# USB2_0_Connector.net
KiCad netlist of a schematic drawn in Altium Designer
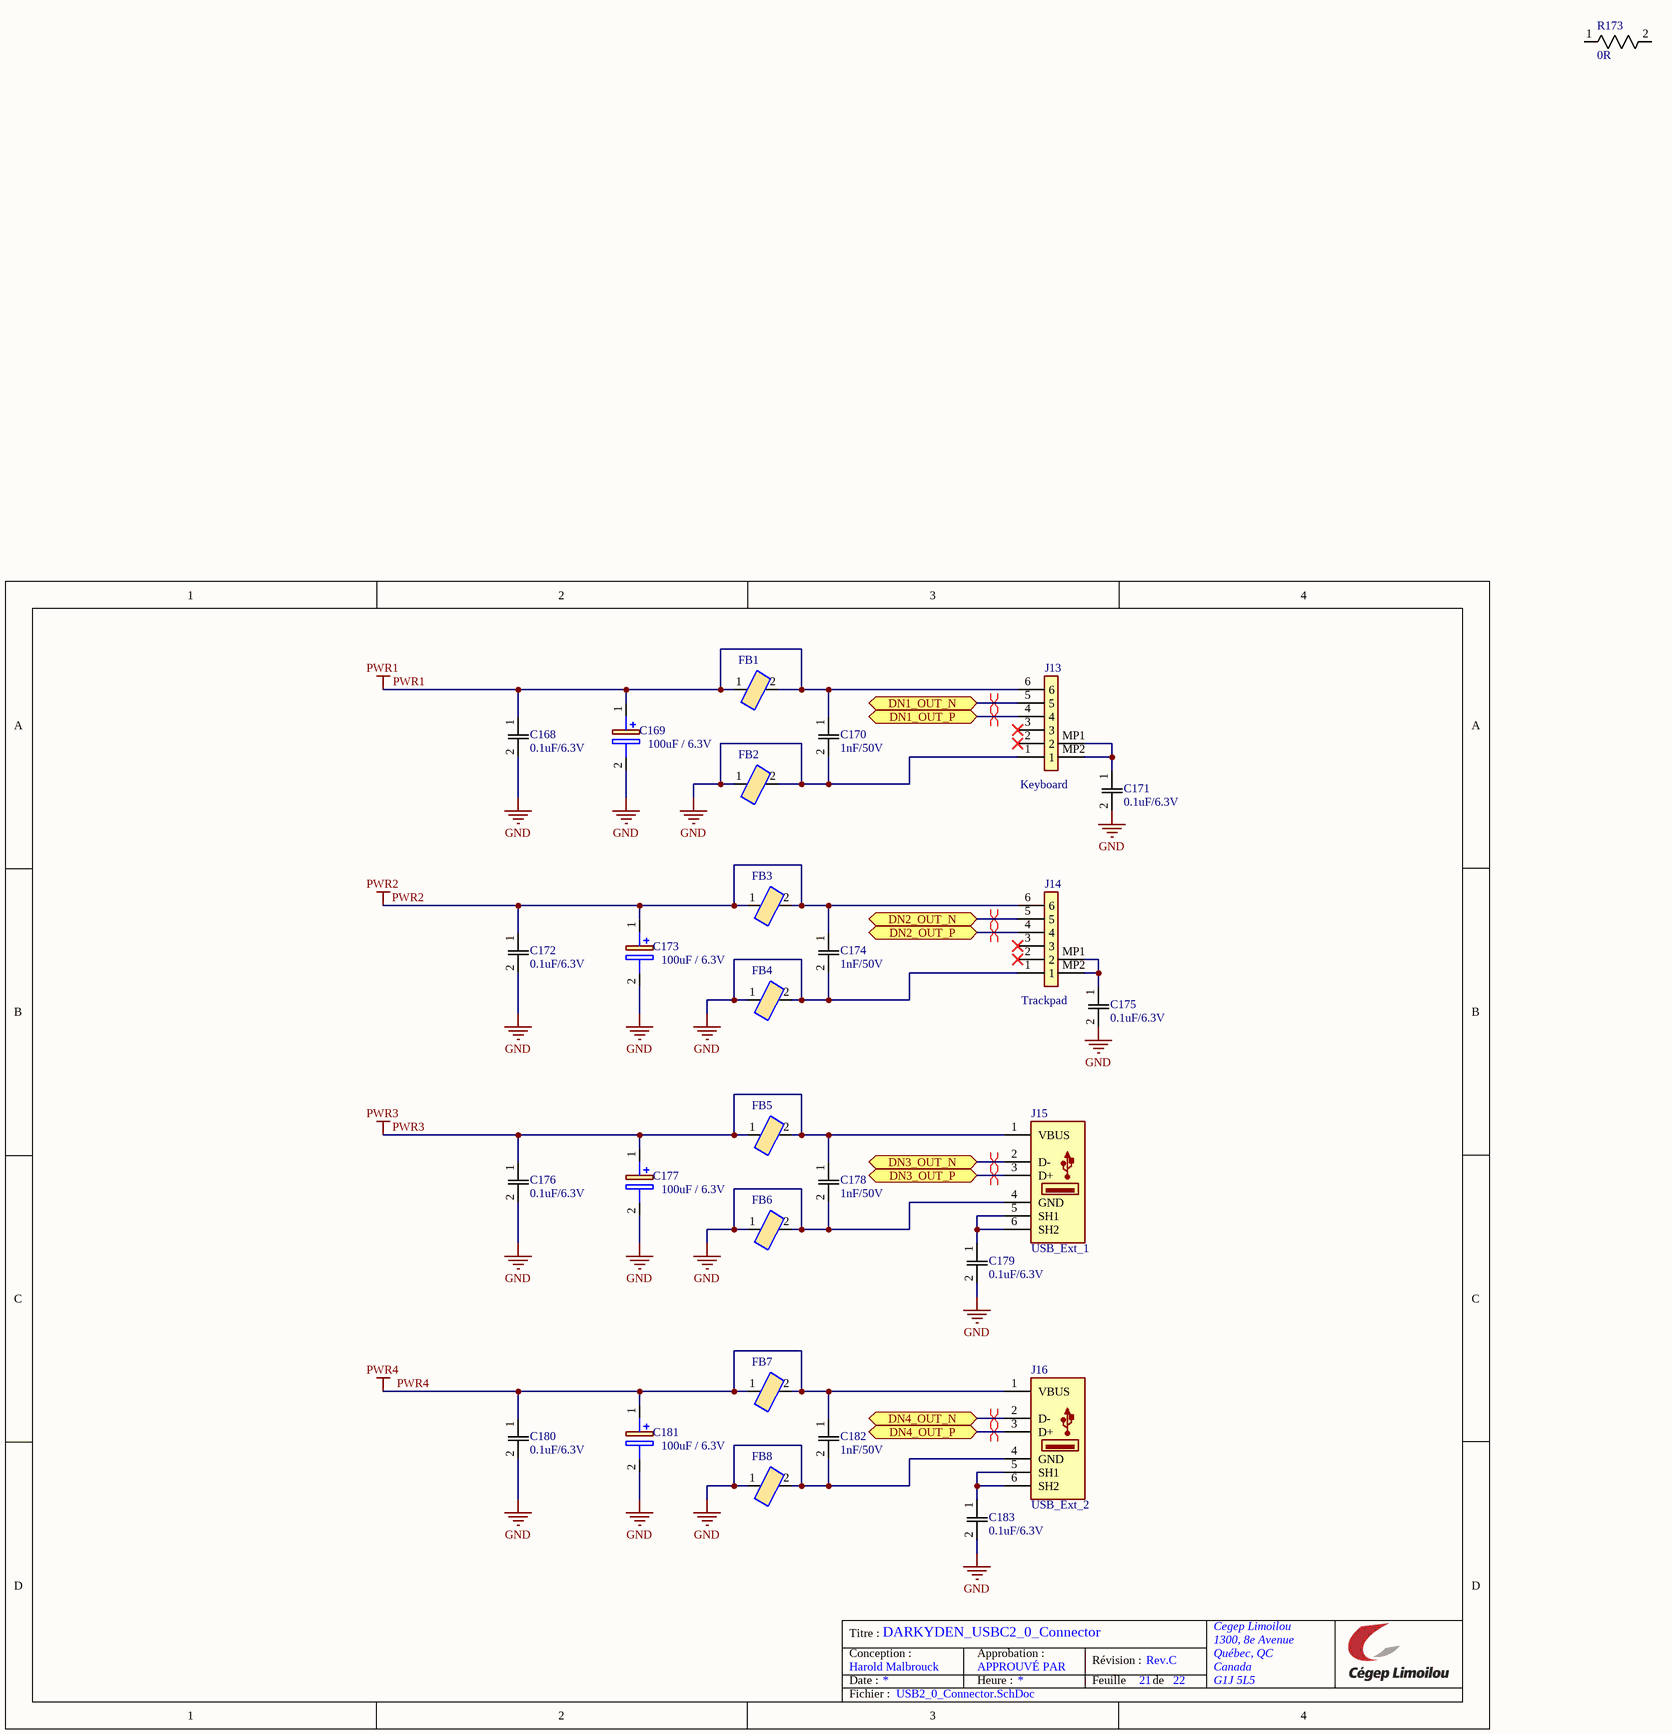
[diagram p0: USB2_0_Connector.SchDoc]

(export (version "E")
  (design (tool "Eeschema 10.0.6"))
  (components
    (comp (ref "C168")
      (value "0.1uF/6.3V")
      (footprint "SamacSys:C0805")
      (description "0.1uF 6.3V X7R 10% Pad SMD 0805 125C T/R")
      (fields
        (field (name "MANUFACTURER_PART_NUMBER") "C0805C104K9RACTU")
        (field (name "MOUSER PART NUMBER") "80-C0805C104K9R")
      )
      (libsource (lib "SamacSys") (part "C0805C104K9RACTU"))
    )
    (comp (ref "C169")
      (value "100uF / 6.3V")
      (footprint "SamacSys:EEE0GA101SR")
      (description "100uF 6.3V 20% Cap Aluminum Lytic  SMD 0.36 Ohm 240mA 2000h 105C Automotive T/R")
      (fields
        (field (name "MANUFACTURER_PART_NUMBER") "EEE-FPJ101UAR")
        (field (name "MOUSER PART NUMBER") "667-EEE-FPJ101UAR")
      )
      (libsource (lib "SamacSys") (part "EEE-FPJ101UAR"))
    )
    (comp (ref "C170")
      (value "1nF/50V")
      (footprint "SamacSys:CAPC2012X88N")
      (description "Multilayer Ceramic Capacitor 1000 Pf 50 V ½ 10% X7R 0805 [2012 Metric]")
      (fields
        (field (name "MANUFACTURER_PART_NUMBER") "C0805C102K5RAC-TU")
        (field (name "MANUFACTURER") "KEMET")
      )
      (libsource (lib "SamacSys") (part "C0805C102K5RACTU"))
    )
    (comp (ref "C171")
      (value "0.1uF/6.3V")
      (footprint "SamacSys:C0805")
      (description "0.1uF 6.3V X7R 10% Pad SMD 0805 125C T/R")
      (fields
        (field (name "MANUFACTURER_PART_NUMBER") "C0805C104K9RACTU")
        (field (name "MOUSER PART NUMBER") "80-C0805C104K9R")
      )
      (libsource (lib "SamacSys") (part "C0805C104K9RACTU"))
    )
    (comp (ref "C172")
      (value "0.1uF/6.3V")
      (footprint "SamacSys:C0805")
      (description "0.1uF 6.3V X7R 10% Pad SMD 0805 125C T/R")
      (fields
        (field (name "MANUFACTURER_PART_NUMBER") "C0805C104K9RACTU")
        (field (name "MOUSER PART NUMBER") "80-C0805C104K9R")
      )
      (libsource (lib "SamacSys") (part "C0805C104K9RACTU"))
    )
    (comp (ref "C173")
      (value "100uF / 6.3V")
      (footprint "SamacSys:EEE0GA101SR")
      (description "100uF 6.3V 20% Cap Aluminum Lytic  SMD 0.36 Ohm 240mA 2000h 105C Automotive T/R")
      (fields
        (field (name "MANUFACTURER_PART_NUMBER") "EEE-FPJ101UAR")
        (field (name "MOUSER PART NUMBER") "667-EEE-FPJ101UAR")
      )
      (libsource (lib "SamacSys") (part "EEE-FPJ101UAR"))
    )
    (comp (ref "C174")
      (value "1nF/50V")
      (footprint "SamacSys:CAPC2012X88N")
      (description "Multilayer Ceramic Capacitor 1000 Pf 50 V ½ 10% X7R 0805 [2012 Metric]")
      (fields
        (field (name "MANUFACTURER_PART_NUMBER") "C0805C102K5RAC-TU")
        (field (name "MANUFACTURER") "KEMET")
      )
      (libsource (lib "SamacSys") (part "C0805C102K5RACTU"))
    )
    (comp (ref "C175")
      (value "0.1uF/6.3V")
      (footprint "SamacSys:C0805")
      (description "0.1uF 6.3V X7R 10% Pad SMD 0805 125C T/R")
      (fields
        (field (name "MANUFACTURER_PART_NUMBER") "C0805C104K9RACTU")
        (field (name "MOUSER PART NUMBER") "80-C0805C104K9R")
      )
      (libsource (lib "SamacSys") (part "C0805C104K9RACTU"))
    )
    (comp (ref "C176")
      (value "0.1uF/6.3V")
      (footprint "SamacSys:C0805")
      (description "0.1uF 6.3V X7R 10% Pad SMD 0805 125C T/R")
      (fields
        (field (name "MANUFACTURER_PART_NUMBER") "C0805C104K9RACTU")
        (field (name "MOUSER PART NUMBER") "80-C0805C104K9R")
      )
      (libsource (lib "SamacSys") (part "C0805C104K9RACTU"))
    )
    (comp (ref "C177")
      (value "100uF / 6.3V")
      (footprint "SamacSys:EEE0GA101SR")
      (description "100uF 6.3V 20% Cap Aluminum Lytic  SMD 0.36 Ohm 240mA 2000h 105C Automotive T/R")
      (fields
        (field (name "MANUFACTURER_PART_NUMBER") "EEE-FPJ101UAR")
        (field (name "MOUSER PART NUMBER") "667-EEE-FPJ101UAR")
      )
      (libsource (lib "SamacSys") (part "EEE-FPJ101UAR"))
    )
    (comp (ref "C178")
      (value "1nF/50V")
      (footprint "SamacSys:CAPC2012X88N")
      (description "Multilayer Ceramic Capacitor 1000 Pf 50 V ½ 10% X7R 0805 [2012 Metric]")
      (fields
        (field (name "MANUFACTURER_PART_NUMBER") "C0805C102K5RAC-TU")
        (field (name "MANUFACTURER") "KEMET")
      )
      (libsource (lib "SamacSys") (part "C0805C102K5RACTU"))
    )
    (comp (ref "C179")
      (value "0.1uF/6.3V")
      (footprint "SamacSys:C0805")
      (description "0.1uF 6.3V X7R 10% Pad SMD 0805 125C T/R")
      (fields
        (field (name "MANUFACTURER_PART_NUMBER") "C0805C104K9RACTU")
        (field (name "MOUSER PART NUMBER") "80-C0805C104K9R")
      )
      (libsource (lib "SamacSys") (part "C0805C104K9RACTU"))
    )
    (comp (ref "C180")
      (value "0.1uF/6.3V")
      (footprint "SamacSys:C0805")
      (description "0.1uF 6.3V X7R 10% Pad SMD 0805 125C T/R")
      (fields
        (field (name "MANUFACTURER_PART_NUMBER") "C0805C104K9RACTU")
        (field (name "MOUSER PART NUMBER") "80-C0805C104K9R")
      )
      (libsource (lib "SamacSys") (part "C0805C104K9RACTU"))
    )
    (comp (ref "C181")
      (value "100uF / 6.3V")
      (footprint "SamacSys:EEE0GA101SR")
      (description "100uF 6.3V 20% Cap Aluminum Lytic  SMD 0.36 Ohm 240mA 2000h 105C Automotive T/R")
      (fields
        (field (name "MANUFACTURER_PART_NUMBER") "EEE-FPJ101UAR")
        (field (name "MOUSER PART NUMBER") "667-EEE-FPJ101UAR")
      )
      (libsource (lib "SamacSys") (part "EEE-FPJ101UAR"))
    )
    (comp (ref "C182")
      (value "1nF/50V")
      (footprint "SamacSys:CAPC2012X88N")
      (description "Multilayer Ceramic Capacitor 1000 Pf 50 V ½ 10% X7R 0805 [2012 Metric]")
      (fields
        (field (name "MANUFACTURER_PART_NUMBER") "C0805C102K5RAC-TU")
        (field (name "MANUFACTURER") "KEMET")
      )
      (libsource (lib "SamacSys") (part "C0805C102K5RACTU"))
    )
    (comp (ref "C183")
      (value "0.1uF/6.3V")
      (footprint "SamacSys:C0805")
      (description "0.1uF 6.3V X7R 10% Pad SMD 0805 125C T/R")
      (fields
        (field (name "MANUFACTURER_PART_NUMBER") "C0805C104K9RACTU")
        (field (name "MOUSER PART NUMBER") "80-C0805C104K9R")
      )
      (libsource (lib "SamacSys") (part "C0805C104K9RACTU"))
    )
    (comp (ref "FB1")
      (value "220R / 100MHz")
      (footprint "SamacSys:BLM18SP221SN1B")
      (description "Ferrite Beads Multi-Layer 220Ohm 25% 100MHz 2A 50mOhm DCR 0603 Paper T/R")
      (fields
        (field (name "MANUFACTURER_PART_NUMBER") "BLM18EG221SN1D")
        (field (name "MOUSER PART NUMBER") "81-BLM18EG221SN1D")
      )
      (libsource (lib "SamacSys") (part "BLM18EG221SN1D"))
    )
    (comp (ref "FB2")
      (value "220R / 100MHz")
      (footprint "SamacSys:BLM18SP221SN1B")
      (description "Ferrite Beads Multi-Layer 220Ohm 25% 100MHz 2A 50mOhm DCR 0603 Paper T/R")
      (fields
        (field (name "MANUFACTURER_PART_NUMBER") "BLM18EG221SN1D")
        (field (name "MOUSER PART NUMBER") "81-BLM18EG221SN1D")
      )
      (libsource (lib "SamacSys") (part "BLM18EG221SN1D"))
    )
    (comp (ref "FB3")
      (value "220R / 100MHz")
      (footprint "SamacSys:BLM18SP221SN1B")
      (description "Ferrite Beads Multi-Layer 220Ohm 25% 100MHz 2A 50mOhm DCR 0603 Paper T/R")
      (fields
        (field (name "MANUFACTURER_PART_NUMBER") "BLM18EG221SN1D")
        (field (name "MOUSER PART NUMBER") "81-BLM18EG221SN1D")
      )
      (libsource (lib "SamacSys") (part "BLM18EG221SN1D"))
    )
    (comp (ref "FB4")
      (value "220R / 100MHz")
      (footprint "SamacSys:BLM18SP221SN1B")
      (description "Ferrite Beads Multi-Layer 220Ohm 25% 100MHz 2A 50mOhm DCR 0603 Paper T/R")
      (fields
        (field (name "MANUFACTURER_PART_NUMBER") "BLM18EG221SN1D")
        (field (name "MOUSER PART NUMBER") "81-BLM18EG221SN1D")
      )
      (libsource (lib "SamacSys") (part "BLM18EG221SN1D"))
    )
    (comp (ref "FB5")
      (value "220R / 100MHz")
      (footprint "SamacSys:BLM18SP221SN1B")
      (description "Ferrite Beads Multi-Layer 220Ohm 25% 100MHz 2A 50mOhm DCR 0603 Paper T/R")
      (fields
        (field (name "MANUFACTURER_PART_NUMBER") "BLM18EG221SN1D")
        (field (name "MOUSER PART NUMBER") "81-BLM18EG221SN1D")
      )
      (libsource (lib "SamacSys") (part "BLM18EG221SN1D"))
    )
    (comp (ref "FB6")
      (value "220R / 100MHz")
      (footprint "SamacSys:BLM18SP221SN1B")
      (description "Ferrite Beads Multi-Layer 220Ohm 25% 100MHz 2A 50mOhm DCR 0603 Paper T/R")
      (fields
        (field (name "MANUFACTURER_PART_NUMBER") "BLM18EG221SN1D")
        (field (name "MOUSER PART NUMBER") "81-BLM18EG221SN1D")
      )
      (libsource (lib "SamacSys") (part "BLM18EG221SN1D"))
    )
    (comp (ref "FB7")
      (value "220R / 100MHz")
      (footprint "SamacSys:BLM18SP221SN1B")
      (description "Ferrite Beads Multi-Layer 220Ohm 25% 100MHz 2A 50mOhm DCR 0603 Paper T/R")
      (fields
        (field (name "MANUFACTURER_PART_NUMBER") "BLM18EG221SN1D")
        (field (name "MOUSER PART NUMBER") "81-BLM18EG221SN1D")
      )
      (libsource (lib "SamacSys") (part "BLM18EG221SN1D"))
    )
    (comp (ref "FB8")
      (value "220R / 100MHz")
      (footprint "SamacSys:BLM18SP221SN1B")
      (description "Ferrite Beads Multi-Layer 220Ohm 25% 100MHz 2A 50mOhm DCR 0603 Paper T/R")
      (fields
        (field (name "MANUFACTURER_PART_NUMBER") "BLM18EG221SN1D")
        (field (name "MOUSER PART NUMBER") "81-BLM18EG221SN1D")
      )
      (libsource (lib "SamacSys") (part "BLM18EG221SN1D"))
    )
    (comp (ref "J13")
      (value "Keyboard")
      (footprint "SamacSys:23287026")
      (description "FPC Connector; 0.5mm pitch dual contact back flip FPC, 6pos ¦ TE Connectivity 2328702-6")
      (fields
        (field (name "MANUFACTURER_PART_NUMBER") "2328702-6")
        (field (name "MOUSER PART NUMBER") "571-2328702-6")
      )
      (libsource (lib "SamacSys") (part "2328702-6"))
    )
    (comp (ref "J14")
      (value "Trackpad")
      (footprint "SamacSys:23287026")
      (description "FPC Connector; 0.5mm pitch dual contact back flip FPC, 6pos ¦ TE Connectivity 2328702-6")
      (fields
        (field (name "MANUFACTURER_PART_NUMBER") "2328702-6")
        (field (name "MOUSER PART NUMBER") "571-2328702-6")
      )
      (libsource (lib "SamacSys") (part "2328702-6"))
    )
    (comp (ref "J15")
      (value "USB_Ext_1")
      (footprint "SamacSys:TECONN-4POS-USB")
      (description "USB-A (USB TYPE-A) USB 2.0 Receptacle Connector 4 Position Through Hole, Right Angle")
      (fields
        (field (name "MANUFACTURER_PART_NUMBER") "292303-1")
        (field (name "MOUSER PART NUMBER") "571-292303-1")
      )
      (libsource (lib "SamacSys") (part "292303-1"))
    )
    (comp (ref "J16")
      (value "USB_Ext_2")
      (footprint "SamacSys:TECONN-4POS-USB")
      (description "USB-A (USB TYPE-A) USB 2.0 Receptacle Connector 4 Position Through Hole, Right Angle")
      (fields
        (field (name "MANUFACTURER_PART_NUMBER") "292303-1")
        (field (name "MOUSER PART NUMBER") "571-292303-1")
      )
      (libsource (lib "SamacSys") (part "292303-1"))
    )
    (comp (ref "R173")
      (value "0R")
      (footprint "SamacSys:ERJ3EKF1000V")
      (description "Zero Ohm Resistor, Jumper, 0603 [1608 Metric], Thick Film, 100 mW, 1 A, Surface Mount")
      (fields
        (field (name "MANUFACTURER_PART_NUMBER") "ERJ-3GEY0R00V")
        (field (name "MOUSER PART NUMBER") "667-ERJ-3GEY0R00V")
      )
      (libsource (lib "SamacSys") (part "ERJ-3GEY0R00V"))
    )
  )
  (nets
    (net (code "1") (name "/DN1_OUT_N") (class "Default")
      (node (ref "J13") (pin "5") (pinfunction "5_5") (pintype "passive"))
    )
    (net (code "2") (name "/DN1_OUT_P") (class "Default")
      (node (ref "J13") (pin "4") (pinfunction "4_4") (pintype "passive"))
    )
    (net (code "3") (name "/DN2_OUT_N") (class "Default")
      (node (ref "J14") (pin "5") (pinfunction "5_5") (pintype "passive"))
    )
    (net (code "4") (name "/DN2_OUT_P") (class "Default")
      (node (ref "J14") (pin "4") (pinfunction "4_4") (pintype "passive"))
    )
    (net (code "5") (name "/DN3_OUT_N") (class "Default")
      (node (ref "J15") (pin "2") (pinfunction "D-_2") (pintype "passive"))
    )
    (net (code "6") (name "/DN3_OUT_P") (class "Default")
      (node (ref "J15") (pin "3") (pinfunction "D+_3") (pintype "passive"))
    )
    (net (code "7") (name "/DN4_OUT_N") (class "Default")
      (node (ref "J16") (pin "2") (pinfunction "D-_2") (pintype "passive"))
    )
    (net (code "8") (name "/DN4_OUT_P") (class "Default")
      (node (ref "J16") (pin "3") (pinfunction "D+_3") (pintype "passive"))
    )
    (net (code "9") (name "GND") (class "Default")
      (node (ref "C168") (pin "2") (pinfunction "2_2") (pintype "passive"))
      (node (ref "C169") (pin "2") (pinfunction "-_2") (pintype "passive"))
      (node (ref "C170") (pin "2") (pinfunction "2_2") (pintype "passive"))
      (node (ref "C171") (pin "2") (pinfunction "2_2") (pintype "passive"))
      (node (ref "C172") (pin "2") (pinfunction "2_2") (pintype "passive"))
      (node (ref "C173") (pin "2") (pinfunction "-_2") (pintype "passive"))
      (node (ref "C174") (pin "2") (pinfunction "2_2") (pintype "passive"))
      (node (ref "C175") (pin "2") (pinfunction "2_2") (pintype "passive"))
      (node (ref "C176") (pin "2") (pinfunction "2_2") (pintype "passive"))
      (node (ref "C177") (pin "2") (pinfunction "-_2") (pintype "passive"))
      (node (ref "C178") (pin "2") (pinfunction "2_2") (pintype "passive"))
      (node (ref "C179") (pin "2") (pinfunction "2_2") (pintype "passive"))
      (node (ref "C180") (pin "2") (pinfunction "2_2") (pintype "passive"))
      (node (ref "C181") (pin "2") (pinfunction "-_2") (pintype "passive"))
      (node (ref "C182") (pin "2") (pinfunction "2_2") (pintype "passive"))
      (node (ref "C183") (pin "2") (pinfunction "2_2") (pintype "passive"))
      (node (ref "FB2") (pin "1") (pinfunction "1_1") (pintype "passive"))
      (node (ref "FB2") (pin "2") (pinfunction "2_2") (pintype "passive"))
      (node (ref "FB4") (pin "1") (pinfunction "1_1") (pintype "passive"))
      (node (ref "FB4") (pin "2") (pinfunction "2_2") (pintype "passive"))
      (node (ref "FB6") (pin "1") (pinfunction "1_1") (pintype "passive"))
      (node (ref "FB6") (pin "2") (pinfunction "2_2") (pintype "passive"))
      (node (ref "FB8") (pin "1") (pinfunction "1_1") (pintype "passive"))
      (node (ref "FB8") (pin "2") (pinfunction "2_2") (pintype "passive"))
      (node (ref "J13") (pin "1") (pinfunction "1_1") (pintype "passive"))
      (node (ref "J14") (pin "1") (pinfunction "1_1") (pintype "passive"))
      (node (ref "J15") (pin "4") (pinfunction "GND_4") (pintype "passive"))
      (node (ref "J16") (pin "4") (pinfunction "GND_4") (pintype "passive"))
    )
    (net (code "10") (name "Net-(C171-Pad1)") (class "Default")
      (node (ref "C171") (pin "1") (pinfunction "1_1") (pintype "passive"))
      (node (ref "J13") (pin "MP1") (pinfunction "MP1_MP1") (pintype "passive"))
      (node (ref "J13") (pin "MP2") (pinfunction "MP2_MP2") (pintype "passive"))
    )
    (net (code "11") (name "Net-(C175-Pad1)") (class "Default")
      (node (ref "C175") (pin "1") (pinfunction "1_1") (pintype "passive"))
      (node (ref "J14") (pin "MP1") (pinfunction "MP1_MP1") (pintype "passive"))
      (node (ref "J14") (pin "MP2") (pinfunction "MP2_MP2") (pintype "passive"))
    )
    (net (code "12") (name "Net-(J15-SH1)") (class "Default")
      (node (ref "C179") (pin "1") (pinfunction "1_1") (pintype "passive"))
      (node (ref "J15") (pin "5") (pinfunction "SH1_5") (pintype "passive"))
      (node (ref "J15") (pin "6") (pinfunction "SH2_6") (pintype "passive"))
    )
    (net (code "13") (name "Net-(J16-SH1)") (class "Default")
      (node (ref "C183") (pin "1") (pinfunction "1_1") (pintype "passive"))
      (node (ref "J16") (pin "5") (pinfunction "SH1_5") (pintype "passive"))
      (node (ref "J16") (pin "6") (pinfunction "SH2_6") (pintype "passive"))
    )
    (net (code "14") (name "PWR1") (class "Default")
      (node (ref "C168") (pin "1") (pinfunction "1_1") (pintype "passive"))
      (node (ref "C169") (pin "1") (pinfunction "+_1") (pintype "passive"))
      (node (ref "C170") (pin "1") (pinfunction "1_1") (pintype "passive"))
      (node (ref "FB1") (pin "1") (pinfunction "1_1") (pintype "passive"))
      (node (ref "FB1") (pin "2") (pinfunction "2_2") (pintype "passive"))
      (node (ref "J13") (pin "6") (pinfunction "6_6") (pintype "passive"))
    )
    (net (code "15") (name "PWR2") (class "Default")
      (node (ref "C172") (pin "1") (pinfunction "1_1") (pintype "passive"))
      (node (ref "C173") (pin "1") (pinfunction "+_1") (pintype "passive"))
      (node (ref "C174") (pin "1") (pinfunction "1_1") (pintype "passive"))
      (node (ref "FB3") (pin "1") (pinfunction "1_1") (pintype "passive"))
      (node (ref "FB3") (pin "2") (pinfunction "2_2") (pintype "passive"))
      (node (ref "J14") (pin "6") (pinfunction "6_6") (pintype "passive"))
    )
    (net (code "16") (name "PWR3") (class "Default")
      (node (ref "C176") (pin "1") (pinfunction "1_1") (pintype "passive"))
      (node (ref "C177") (pin "1") (pinfunction "+_1") (pintype "passive"))
      (node (ref "C178") (pin "1") (pinfunction "1_1") (pintype "passive"))
      (node (ref "FB5") (pin "1") (pinfunction "1_1") (pintype "passive"))
      (node (ref "FB5") (pin "2") (pinfunction "2_2") (pintype "passive"))
      (node (ref "J15") (pin "1") (pinfunction "VBUS_1") (pintype "passive"))
    )
    (net (code "17") (name "PWR4") (class "Default")
      (node (ref "C180") (pin "1") (pinfunction "1_1") (pintype "passive"))
      (node (ref "C181") (pin "1") (pinfunction "+_1") (pintype "passive"))
      (node (ref "C182") (pin "1") (pinfunction "1_1") (pintype "passive"))
      (node (ref "FB7") (pin "1") (pinfunction "1_1") (pintype "passive"))
      (node (ref "FB7") (pin "2") (pinfunction "2_2") (pintype "passive"))
      (node (ref "J16") (pin "1") (pinfunction "VBUS_1") (pintype "passive"))
    )
    (net (code "18") (name "unconnected-(J13-Pad2)") (class "Default")
      (node (ref "J13") (pin "2") (pinfunction "2_2") (pintype "passive+no_connect"))
    )
    (net (code "19") (name "unconnected-(J13-Pad3)") (class "Default")
      (node (ref "J13") (pin "3") (pinfunction "3_3") (pintype "passive+no_connect"))
    )
    (net (code "20") (name "unconnected-(J14-Pad2)") (class "Default")
      (node (ref "J14") (pin "2") (pinfunction "2_2") (pintype "passive+no_connect"))
    )
    (net (code "21") (name "unconnected-(J14-Pad3)") (class "Default")
      (node (ref "J14") (pin "3") (pinfunction "3_3") (pintype "passive+no_connect"))
    )
    (net (code "22") (name "unconnected-(R173-Pad1)") (class "Default")
      (node (ref "R173") (pin "1") (pinfunction "1_1") (pintype "passive"))
    )
    (net (code "23") (name "unconnected-(R173-Pad2)") (class "Default")
      (node (ref "R173") (pin "2") (pinfunction "2_2") (pintype "passive"))
    )
  )
)
